# Full_Water_Level_Detector_Project_Schema.net
KiCad netlist of a schematic drawn in EAGLE
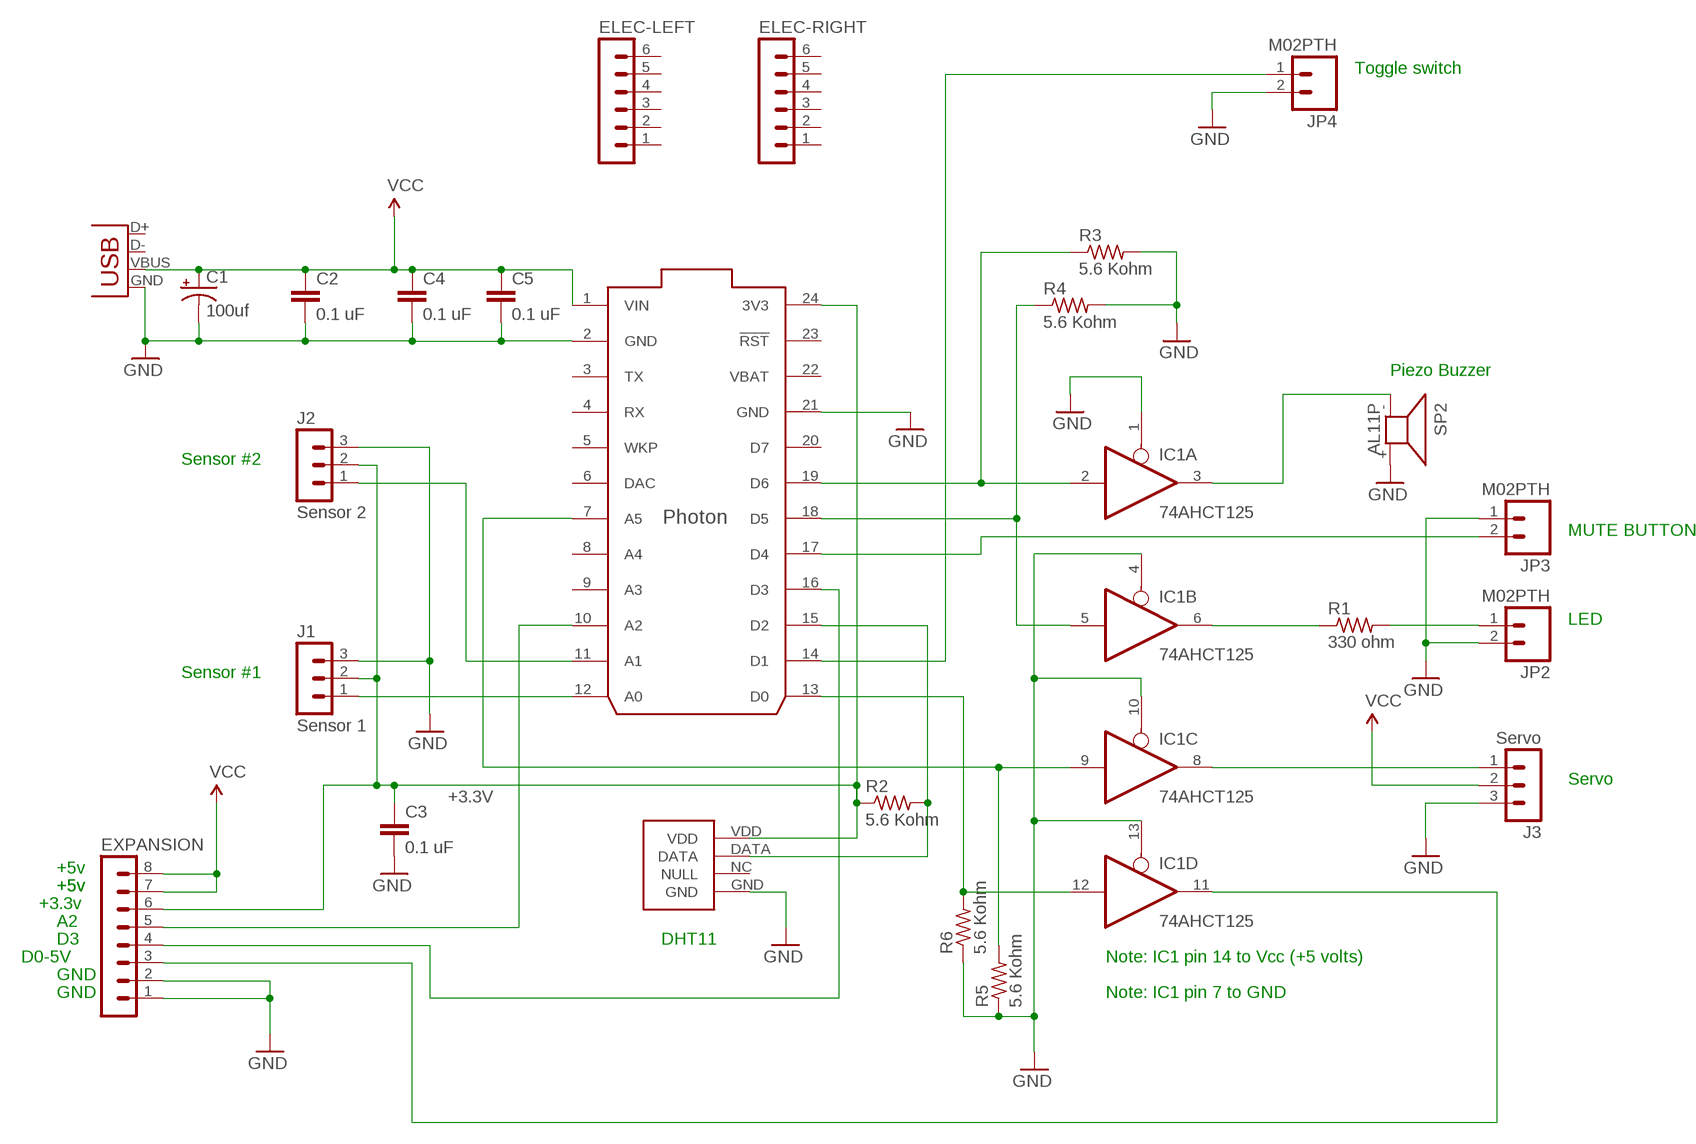
[diagram p0: schematic, sheet 1]

(export (version "E")
  (design (tool "Eeschema 10.0.6"))
  (components
    (comp (ref "C1")
      (value "100uf")
      (footprint "eagle-import:CPOL-RADIAL-100UF-25V")
      (libsource (lib "eagle-import") (part "CAP_POLPTH1"))
    )
    (comp (ref "C2")
      (value "0.1 uF")
      (footprint "eagle-import:CAP-PTH-SMALL")
      (libsource (lib "eagle-import") (part "CAPPTH"))
    )
    (comp (ref "C3")
      (value "0.1 uF")
      (footprint "eagle-import:CAP-PTH-SMALL")
      (libsource (lib "eagle-import") (part "CAPPTH"))
    )
    (comp (ref "C4")
      (value "0.1 uF")
      (footprint "eagle-import:CAP-PTH-SMALL")
      (libsource (lib "eagle-import") (part "CAPPTH"))
    )
    (comp (ref "C5")
      (value "0.1 uF")
      (footprint "eagle-import:CAP-PTH-SMALL")
      (libsource (lib "eagle-import") (part "CAPPTH"))
    )
    (comp (ref "ELEC-LEFT")
      (value "MA06-1")
      (footprint "eagle-import:MA06-1")
      (libsource (lib "eagle-import") (part "MA06-1"))
    )
    (comp (ref "ELEC-RIGHT")
      (value "MA06-1")
      (footprint "eagle-import:MA06-1")
      (libsource (lib "eagle-import") (part "MA06-1"))
    )
    (comp (ref "EXPANSION")
      (value "MA08-1")
      (footprint "eagle-import:MA08-1")
      (libsource (lib "eagle-import") (part "MA08-1"))
    )
    (comp (ref "IC1")
      (value "74AHCT125")
      (footprint "eagle-import:DIL14")
      (libsource (lib "eagle-import") (part "74125N"))
    )
    (comp (ref "J1")
      (value "Sensor 1")
      (footprint "eagle-import:MA03-1")
      (libsource (lib "eagle-import") (part "MA03-1"))
    )
    (comp (ref "J2")
      (value "Sensor 2")
      (footprint "eagle-import:MA03-1")
      (libsource (lib "eagle-import") (part "MA03-1"))
    )
    (comp (ref "J3")
      (value "Servo")
      (footprint "eagle-import:MA03-1")
      (libsource (lib "eagle-import") (part "MA03-1"))
    )
    (comp (ref "JP1")
      (value "USB-B")
      (footprint "eagle-import:USB-B-PTH")
      (libsource (lib "eagle-import") (part "USBPTH"))
    )
    (comp (ref "JP2")
      (value "M02PTH")
      (footprint "eagle-import:1X02")
      (libsource (lib "eagle-import") (part "M02PTH"))
    )
    (comp (ref "JP3")
      (value "M02PTH")
      (footprint "eagle-import:1X02")
      (libsource (lib "eagle-import") (part "M02PTH"))
    )
    (comp (ref "JP4")
      (value "M02PTH")
      (footprint "eagle-import:1X02")
      (libsource (lib "eagle-import") (part "M02PTH"))
    )
    (comp (ref "R1")
      (value "330 ohm")
      (footprint "eagle-import:0309_12")
      (libsource (lib "eagle-import") (part "R-US_0309/12"))
    )
    (comp (ref "R2")
      (value "5.6 Kohm")
      (footprint "eagle-import:0309_12")
      (libsource (lib "eagle-import") (part "R-US_0309/12"))
    )
    (comp (ref "R3")
      (value "5.6 Kohm")
      (footprint "eagle-import:0309_12")
      (libsource (lib "eagle-import") (part "R-US_0309/12"))
    )
    (comp (ref "R4")
      (value "5.6 Kohm")
      (footprint "eagle-import:0309_12")
      (libsource (lib "eagle-import") (part "R-US_0309/12"))
    )
    (comp (ref "R5")
      (value "5.6 Kohm")
      (footprint "eagle-import:0309_12")
      (libsource (lib "eagle-import") (part "R-US_0309/12"))
    )
    (comp (ref "R6")
      (value "5.6 Kohm")
      (footprint "eagle-import:0309_12")
      (libsource (lib "eagle-import") (part "R-US_0309/12"))
    )
    (comp (ref "SP2")
      (value "AL11P")
      (footprint "eagle-import:AL11P")
      (libsource (lib "eagle-import") (part "AL11P"))
    )
    (comp (ref "U$1")
      (value "PHOTON_SMD")
      (footprint "eagle-import:PHOTON_SMD")
      (libsource (lib "eagle-import") (part "PHOTON_SMD"))
    )
    (comp (ref "U$2")
      (value "DHT22")
      (footprint "eagle-import:DHT22")
      (libsource (lib "eagle-import") (part "DHT22"))
    )
  )
  (nets
    (net (code "1") (name "/+3.3V") (class "Default")
      (node (ref "C3") (pin "1") (pinfunction "1_1") (pintype "passive"))
      (node (ref "EXPANSION") (pin "6") (pinfunction "6_6") (pintype "passive"))
      (node (ref "J1") (pin "2") (pinfunction "2_2") (pintype "passive"))
      (node (ref "J2") (pin "2") (pinfunction "2_2") (pintype "passive"))
      (node (ref "R2") (pin "1") (pinfunction "1_1") (pintype "passive"))
      (node (ref "U$1") (pin "24") (pinfunction "3V3_24") (pintype "power_in"))
      (node (ref "U$2") (pin "VDD") (pinfunction "VDD_VDD") (pintype "power_in"))
    )
    (net (code "2") (name "/VBAT") (class "Default")
      (node (ref "U$1") (pin "22") (pinfunction "VBAT_22") (pintype "power_in"))
    )
    (net (code "3") (name "GND") (class "Default")
      (node (ref "C1") (pin "2") (pinfunction "-_2") (pintype "passive"))
      (node (ref "C2") (pin "2") (pinfunction "2_2") (pintype "passive"))
      (node (ref "C3") (pin "2") (pinfunction "2_2") (pintype "passive"))
      (node (ref "C4") (pin "2") (pinfunction "2_2") (pintype "passive"))
      (node (ref "C5") (pin "2") (pinfunction "2_2") (pintype "passive"))
      (node (ref "EXPANSION") (pin "1") (pinfunction "1_1") (pintype "passive"))
      (node (ref "EXPANSION") (pin "2") (pinfunction "2_2") (pintype "passive"))
      (node (ref "IC1") (pin "1") (pinfunction "OE_1") (pintype "input"))
      (node (ref "IC1") (pin "10") (pinfunction "OE_10") (pintype "input"))
      (node (ref "IC1") (pin "13") (pinfunction "OE_13") (pintype "input"))
      (node (ref "IC1") (pin "4") (pinfunction "OE_4") (pintype "input"))
      (node (ref "J1") (pin "3") (pinfunction "3_3") (pintype "passive"))
      (node (ref "J2") (pin "3") (pinfunction "3_3") (pintype "passive"))
      (node (ref "J3") (pin "3") (pinfunction "3_3") (pintype "passive"))
      (node (ref "JP1") (pin "GND") (pinfunction "GND_GND") (pintype "bidirectional"))
      (node (ref "JP2") (pin "2") (pinfunction "2_2") (pintype "passive"))
      (node (ref "JP3") (pin "1") (pinfunction "1_1") (pintype "passive"))
      (node (ref "JP4") (pin "2") (pinfunction "2_2") (pintype "passive"))
      (node (ref "R3") (pin "2") (pinfunction "2_2") (pintype "passive"))
      (node (ref "R4") (pin "2") (pinfunction "2_2") (pintype "passive"))
      (node (ref "R5") (pin "1") (pinfunction "1_1") (pintype "passive"))
      (node (ref "R6") (pin "1") (pinfunction "1_1") (pintype "passive"))
      (node (ref "SP2") (pin "+") (pinfunction "2_+") (pintype "passive"))
      (node (ref "U$1") (pin "2") (pinfunction "GND_2") (pintype "power_in"))
      (node (ref "U$1") (pin "21") (pinfunction "GND_21") (pintype "power_in"))
      (node (ref "U$2") (pin "GND") (pinfunction "GND_GND") (pintype "power_in"))
    )
    (net (code "4") (name "Net-(IC1A-I)") (class "Default")
      (node (ref "IC1") (pin "2") (pinfunction "I_2") (pintype "input"))
      (node (ref "R3") (pin "1") (pinfunction "1_1") (pintype "passive"))
      (node (ref "U$1") (pin "19") (pinfunction "D6_19") (pintype "bidirectional"))
    )
    (net (code "5") (name "Net-(IC1A-O)") (class "Default")
      (node (ref "IC1") (pin "3") (pinfunction "O_3") (pintype "tri_state"))
      (node (ref "SP2") (pin "-") (pinfunction "1_-") (pintype "passive"))
    )
    (net (code "6") (name "Net-(IC1B-I)") (class "Default")
      (node (ref "IC1") (pin "5") (pinfunction "I_5") (pintype "input"))
      (node (ref "R4") (pin "1") (pinfunction "1_1") (pintype "passive"))
      (node (ref "U$1") (pin "18") (pinfunction "D5_18") (pintype "bidirectional"))
    )
    (net (code "7") (name "Net-(IC1B-O)") (class "Default")
      (node (ref "IC1") (pin "6") (pinfunction "O_6") (pintype "tri_state"))
      (node (ref "R1") (pin "1") (pinfunction "1_1") (pintype "passive"))
    )
    (net (code "8") (name "Net-(IC1C-I)") (class "Default")
      (node (ref "IC1") (pin "9") (pinfunction "I_9") (pintype "input"))
      (node (ref "R5") (pin "2") (pinfunction "2_2") (pintype "passive"))
      (node (ref "U$1") (pin "7") (pinfunction "A5_7") (pintype "bidirectional"))
    )
    (net (code "9") (name "Net-(IC1C-O)") (class "Default")
      (node (ref "IC1") (pin "8") (pinfunction "O_8") (pintype "tri_state"))
      (node (ref "J3") (pin "1") (pinfunction "1_1") (pintype "passive"))
    )
    (net (code "10") (name "Net-(IC1D-I)") (class "Default")
      (node (ref "IC1") (pin "12") (pinfunction "I_12") (pintype "input"))
      (node (ref "R6") (pin "2") (pinfunction "2_2") (pintype "passive"))
      (node (ref "U$1") (pin "13") (pinfunction "D0_13") (pintype "bidirectional"))
    )
    (net (code "11") (name "Net-(IC1D-O)") (class "Default")
      (node (ref "EXPANSION") (pin "3") (pinfunction "3_3") (pintype "passive"))
      (node (ref "IC1") (pin "11") (pinfunction "O_11") (pintype "tri_state"))
    )
    (net (code "12") (name "Net-(JP2-Pad1)") (class "Default")
      (node (ref "JP2") (pin "1") (pinfunction "1_1") (pintype "passive"))
      (node (ref "R1") (pin "2") (pinfunction "2_2") (pintype "passive"))
    )
    (net (code "13") (name "Net-(U$1A-A0)") (class "Default")
      (node (ref "J1") (pin "1") (pinfunction "1_1") (pintype "passive"))
      (node (ref "U$1") (pin "12") (pinfunction "A0_12") (pintype "bidirectional"))
    )
    (net (code "14") (name "Net-(U$1A-A1)") (class "Default")
      (node (ref "J2") (pin "1") (pinfunction "1_1") (pintype "passive"))
      (node (ref "U$1") (pin "11") (pinfunction "A1_11") (pintype "bidirectional"))
    )
    (net (code "15") (name "Net-(U$1A-A2)") (class "Default")
      (node (ref "EXPANSION") (pin "5") (pinfunction "5_5") (pintype "passive"))
      (node (ref "U$1") (pin "10") (pinfunction "A2_10") (pintype "bidirectional"))
    )
    (net (code "16") (name "Net-(U$1A-D1)") (class "Default")
      (node (ref "JP4") (pin "1") (pinfunction "1_1") (pintype "passive"))
      (node (ref "U$1") (pin "14") (pinfunction "D1_14") (pintype "bidirectional"))
    )
    (net (code "17") (name "Net-(U$1A-D2)") (class "Default")
      (node (ref "R2") (pin "2") (pinfunction "2_2") (pintype "passive"))
      (node (ref "U$1") (pin "15") (pinfunction "D2_15") (pintype "bidirectional"))
      (node (ref "U$2") (pin "DATA") (pinfunction "DATA_DATA") (pintype "output"))
    )
    (net (code "18") (name "Net-(U$1A-D3)") (class "Default")
      (node (ref "EXPANSION") (pin "4") (pinfunction "4_4") (pintype "passive"))
      (node (ref "U$1") (pin "16") (pinfunction "D3_16") (pintype "bidirectional"))
    )
    (net (code "19") (name "Net-(U$1A-D4)") (class "Default")
      (node (ref "JP3") (pin "2") (pinfunction "2_2") (pintype "passive"))
      (node (ref "U$1") (pin "17") (pinfunction "D4_17") (pintype "bidirectional"))
    )
    (net (code "20") (name "VCC") (class "Default")
      (node (ref "C1") (pin "1") (pinfunction "+_1") (pintype "passive"))
      (node (ref "C2") (pin "1") (pinfunction "1_1") (pintype "passive"))
      (node (ref "C4") (pin "1") (pinfunction "1_1") (pintype "passive"))
      (node (ref "C5") (pin "1") (pinfunction "1_1") (pintype "passive"))
      (node (ref "EXPANSION") (pin "7") (pinfunction "7_7") (pintype "passive"))
      (node (ref "EXPANSION") (pin "8") (pinfunction "8_8") (pintype "passive"))
      (node (ref "J3") (pin "2") (pinfunction "2_2") (pintype "passive"))
      (node (ref "JP1") (pin "VBUS") (pinfunction "VBUS_VBUS") (pintype "bidirectional"))
      (node (ref "U$1") (pin "1") (pinfunction "VIN_1") (pintype "power_in"))
    )
    (net (code "21") (name "unconnected-(ELEC-LEFT-Pad1)") (class "Default")
      (node (ref "ELEC-LEFT") (pin "1") (pinfunction "1_1") (pintype "passive"))
    )
    (net (code "22") (name "unconnected-(ELEC-LEFT-Pad2)") (class "Default")
      (node (ref "ELEC-LEFT") (pin "2") (pinfunction "2_2") (pintype "passive"))
    )
    (net (code "23") (name "unconnected-(ELEC-LEFT-Pad3)") (class "Default")
      (node (ref "ELEC-LEFT") (pin "3") (pinfunction "3_3") (pintype "passive"))
    )
    (net (code "24") (name "unconnected-(ELEC-LEFT-Pad4)") (class "Default")
      (node (ref "ELEC-LEFT") (pin "4") (pinfunction "4_4") (pintype "passive"))
    )
    (net (code "25") (name "unconnected-(ELEC-LEFT-Pad5)") (class "Default")
      (node (ref "ELEC-LEFT") (pin "5") (pinfunction "5_5") (pintype "passive"))
    )
    (net (code "26") (name "unconnected-(ELEC-LEFT-Pad6)") (class "Default")
      (node (ref "ELEC-LEFT") (pin "6") (pinfunction "6_6") (pintype "passive"))
    )
    (net (code "27") (name "unconnected-(ELEC-RIGHT-Pad1)") (class "Default")
      (node (ref "ELEC-RIGHT") (pin "1") (pinfunction "1_1") (pintype "passive"))
    )
    (net (code "28") (name "unconnected-(ELEC-RIGHT-Pad2)") (class "Default")
      (node (ref "ELEC-RIGHT") (pin "2") (pinfunction "2_2") (pintype "passive"))
    )
    (net (code "29") (name "unconnected-(ELEC-RIGHT-Pad3)") (class "Default")
      (node (ref "ELEC-RIGHT") (pin "3") (pinfunction "3_3") (pintype "passive"))
    )
    (net (code "30") (name "unconnected-(ELEC-RIGHT-Pad4)") (class "Default")
      (node (ref "ELEC-RIGHT") (pin "4") (pinfunction "4_4") (pintype "passive"))
    )
    (net (code "31") (name "unconnected-(ELEC-RIGHT-Pad5)") (class "Default")
      (node (ref "ELEC-RIGHT") (pin "5") (pinfunction "5_5") (pintype "passive"))
    )
    (net (code "32") (name "unconnected-(ELEC-RIGHT-Pad6)") (class "Default")
      (node (ref "ELEC-RIGHT") (pin "6") (pinfunction "6_6") (pintype "passive"))
    )
    (net (code "33") (name "unconnected-(JP1-PadD+)") (class "Default")
      (node (ref "JP1") (pin "D+") (pinfunction "D+_D+") (pintype "bidirectional"))
    )
    (net (code "34") (name "unconnected-(JP1-PadD-)") (class "Default")
      (node (ref "JP1") (pin "D-") (pinfunction "D-_D-") (pintype "bidirectional"))
    )
    (net (code "35") (name "unconnected-(U$1A-A3-Pad9)") (class "Default")
      (node (ref "U$1") (pin "9") (pinfunction "A3_9") (pintype "bidirectional"))
    )
    (net (code "36") (name "unconnected-(U$1A-A4-Pad8)") (class "Default")
      (node (ref "U$1") (pin "8") (pinfunction "A4_8") (pintype "bidirectional"))
    )
    (net (code "37") (name "unconnected-(U$1A-D7-Pad20)") (class "Default")
      (node (ref "U$1") (pin "20") (pinfunction "D7_20") (pintype "bidirectional"))
    )
    (net (code "38") (name "unconnected-(U$1A-DAC-Pad6)") (class "Default")
      (node (ref "U$1") (pin "6") (pinfunction "DAC_6") (pintype "bidirectional"))
    )
    (net (code "39") (name "unconnected-(U$1A-RX-Pad4)") (class "Default")
      (node (ref "U$1") (pin "4") (pinfunction "RX_4") (pintype "bidirectional"))
    )
    (net (code "40") (name "unconnected-(U$1A-TX-Pad3)") (class "Default")
      (node (ref "U$1") (pin "3") (pinfunction "TX_3") (pintype "bidirectional"))
    )
    (net (code "41") (name "unconnected-(U$1A-WKP-Pad5)") (class "Default")
      (node (ref "U$1") (pin "5") (pinfunction "WKP_5") (pintype "bidirectional"))
    )
    (net (code "42") (name "unconnected-(U$1A-~{RST}-Pad23)") (class "Default")
      (node (ref "U$1") (pin "23") (pinfunction "~{RST}_23") (pintype "bidirectional"))
    )
    (net (code "43") (name "unconnected-(U$2-NULL-PadNC)") (class "Default")
      (node (ref "U$2") (pin "NC") (pinfunction "NULL_NC") (pintype "no_connect"))
    )
  )
)
